# design.net
KiCad netlist of a schematic drawn in Altium Designer
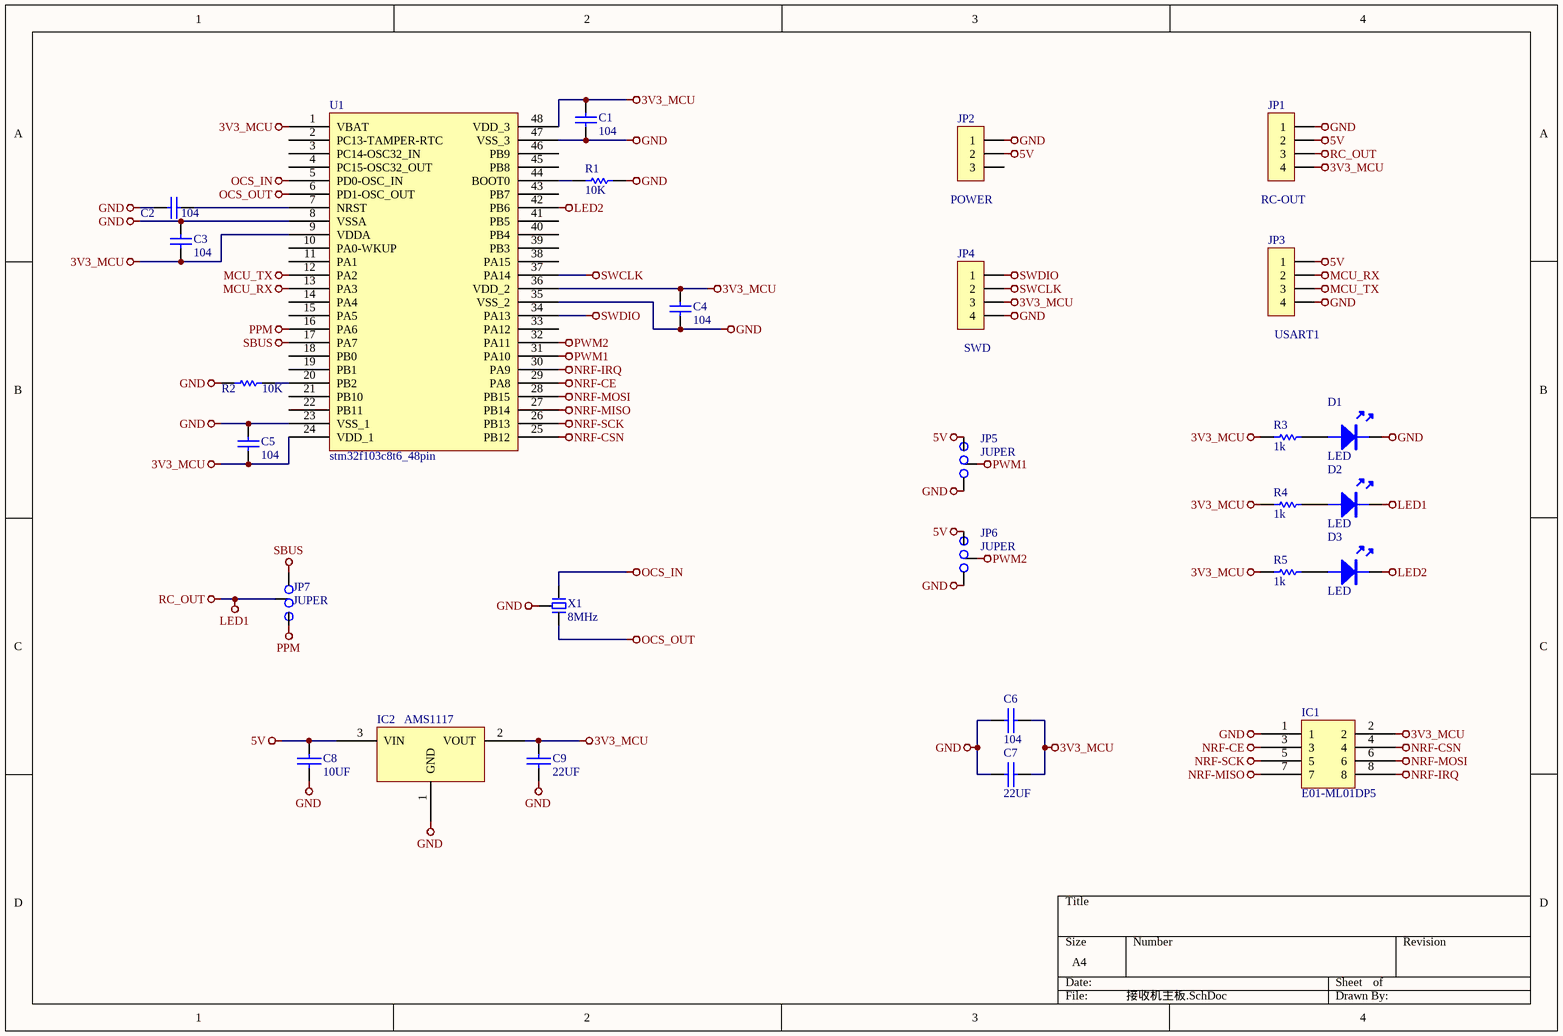
[diagram p0: 接收机主板.SchDoc]

(export (version "E")
  (design (tool "Eeschema 10.0.6"))
  (components
    (comp (ref "C1")
      (value "104")
      (footprint "0603C")
      (fields (field (name "PUBLISHER") "Altium Limited"))
      (libsource (lib "stm32原理图库") (part "Cap"))
    )
    (comp (ref "C2")
      (value "104")
      (footprint "0603C")
      (fields (field (name "PUBLISHER") "Altium Limited"))
      (libsource (lib "stm32原理图库") (part "Cap"))
    )
    (comp (ref "C3")
      (value "104")
      (footprint "0603C")
      (fields (field (name "PUBLISHER") "Altium Limited"))
      (libsource (lib "stm32原理图库") (part "Cap"))
    )
    (comp (ref "C4")
      (value "104")
      (footprint "0603C")
      (fields (field (name "PUBLISHER") "Altium Limited"))
      (libsource (lib "stm32原理图库") (part "Cap"))
    )
    (comp (ref "C5")
      (value "104")
      (footprint "0603C")
      (fields (field (name "PUBLISHER") "Altium Limited"))
      (libsource (lib "stm32原理图库") (part "Cap"))
    )
    (comp (ref "C6")
      (value "104")
      (footprint "0603C")
      (description "无极性电容")
      (libsource (lib "电容") (part "CAP"))
    )
    (comp (ref "C7")
      (value "22UF")
      (footprint "0603C")
      (description "无极性电容")
      (libsource (lib "电容") (part "CAP"))
    )
    (comp (ref "C8")
      (value "10UF")
      (footprint "0603C")
      (description "无极性电容")
      (libsource (lib "电容") (part "CAP"))
    )
    (comp (ref "C9")
      (value "22UF")
      (footprint "0603C")
      (description "无极性电容")
      (libsource (lib "电容") (part "CAP"))
    )
    (comp (ref "D1") (value "LED") (footprint "LED-0603G") (libsource (lib "LED") (part "LED")))
    (comp (ref "D2") (value "LED") (footprint "LED-0603G") (libsource (lib "LED") (part "LED")))
    (comp (ref "D3") (value "LED") (footprint "LED-0603G") (libsource (lib "LED") (part "LED")))
    (comp (ref "IC1")
      (value "E01-ML01DP5")
      (footprint "E01-ML01DP5")
      (description "2.4G无线模块")
      (libsource (lib "飞控接收机主板") (part "E01-ML01DP5"))
    )
    (comp (ref "IC2")
      (value "AMS1117")
      (footprint "AMS1117")
      (description "3V3降压芯片")
      (libsource (lib "飞控主板") (part "AMS1117"))
    )
    (comp (ref "JP1")
      (value "RC-OUT")
      (footprint "SH1.0 S-W-4P")
      (description "4P接插件")
      (fields (field (name "版权归属") "源创客"))
      (libsource (lib "ATKF405 V1.1") (part "Header 4"))
    )
    (comp (ref "JP2")
      (value "POWER")
      (footprint "MX 1.25-WS-3P")
      (description "3P接插件")
      (fields (field (name "版权归属") "源创客"))
      (libsource (lib "ATKF405 V1.1") (part "Header 3"))
    )
    (comp (ref "JP3")
      (value "USART1")
      (footprint "SH1.0 S-W-4P")
      (description "4P接插件")
      (fields (field (name "版权归属") "源创客"))
      (libsource (lib "ATKF405 V1.1") (part "Header 4"))
    )
    (comp (ref "JP4")
      (value "SWD")
      (footprint "SH1.0 S-W-4P")
      (description "4P接插件")
      (fields (field (name "版权归属") "源创客"))
      (libsource (lib "ATKF405 V1.1") (part "Header 4"))
    )
    (comp (ref "JP5")
      (value "JUPER")
      (footprint "JUMPER 3P")
      (description "三点焊盘跳线")
      (libsource (lib "ATKF405 V1.1") (part "JUMPER 3P"))
    )
    (comp (ref "JP6")
      (value "JUPER")
      (footprint "JUMPER 3P")
      (description "三点焊盘跳线")
      (libsource (lib "ATKF405 V1.1") (part "JUMPER 3P"))
    )
    (comp (ref "JP7")
      (value "JUPER")
      (footprint "JUMPER 3P")
      (description "三点焊盘跳线")
      (libsource (lib "ATKF405 V1.1") (part "JUMPER 3P"))
    )
    (comp (ref "R1") (value "10K") (footprint "0402R") (libsource (lib "电阻") (part "RES")))
    (comp (ref "R2") (value "10K") (footprint "0402R") (libsource (lib "电阻") (part "RES")))
    (comp (ref "R3") (value "1k") (footprint "0805R") (libsource (lib "电阻") (part "RES")))
    (comp (ref "R4") (value "1k") (footprint "0805R") (libsource (lib "电阻") (part "RES")))
    (comp (ref "R5") (value "1k") (footprint "0805R") (libsource (lib "电阻") (part "RES")))
    (comp (ref "U1")
      (value "stm32f103c8t6_48pin")
      (footprint "LQFP48 7X7")
      (libsource (lib "stm32原理图库") (part "stm32f103c8t6_48pin"))
    )
    (comp (ref "X1")
      (value "8MHz")
      (footprint "XTAL-3215-3P")
      (description "3脚无源晶振")
      (fields (field (name "版权归属") "源创客"))
      (libsource (lib "ATKF405 V1.1") (part "XTAL-3P"))
    )
  )
  (nets
    (net (code "1") (name "3V3_MCU") (class "Default")
      (node (ref "C1") (pin "2") (pinfunction "2_2") (pintype "passive"))
      (node (ref "C3") (pin "1") (pinfunction "1_1") (pintype "passive"))
      (node (ref "C4") (pin "2") (pinfunction "2_2") (pintype "passive"))
      (node (ref "C5") (pin "1") (pinfunction "1_1") (pintype "passive"))
      (node (ref "C6") (pin "2") (pinfunction "2_2") (pintype "passive"))
      (node (ref "C7") (pin "2") (pinfunction "2_2") (pintype "passive"))
      (node (ref "C9") (pin "2") (pinfunction "2_2") (pintype "passive"))
      (node (ref "IC1") (pin "2") (pinfunction "2_2") (pintype "passive"))
      (node (ref "IC2") (pin "2") (pinfunction "VOUT_2") (pintype "passive"))
      (node (ref "JP1") (pin "4") (pinfunction "4_4") (pintype "passive"))
      (node (ref "JP4") (pin "3") (pinfunction "3_3") (pintype "passive"))
      (node (ref "R3") (pin "1") (pinfunction "1_1") (pintype "passive"))
      (node (ref "R4") (pin "1") (pinfunction "1_1") (pintype "passive"))
      (node (ref "R5") (pin "1") (pinfunction "1_1") (pintype "passive"))
      (node (ref "U1") (pin "1") (pinfunction "VBAT_1") (pintype "passive"))
      (node (ref "U1") (pin "24") (pinfunction "VDD_1_24") (pintype "passive"))
      (node (ref "U1") (pin "36") (pinfunction "VDD_2_36") (pintype "passive"))
      (node (ref "U1") (pin "48") (pinfunction "VDD_3_48") (pintype "passive"))
      (node (ref "U1") (pin "9") (pinfunction "VDDA_9") (pintype "passive"))
    )
    (net (code "2") (name "5V") (class "Default")
      (node (ref "C8") (pin "2") (pinfunction "2_2") (pintype "passive"))
      (node (ref "IC2") (pin "3") (pinfunction "VIN_3") (pintype "passive"))
      (node (ref "JP1") (pin "2") (pinfunction "2_2") (pintype "passive"))
      (node (ref "JP2") (pin "2") (pinfunction "2_2") (pintype "passive"))
      (node (ref "JP3") (pin "1") (pinfunction "1_1") (pintype "passive"))
      (node (ref "JP5") (pin "3") (pinfunction "3_3") (pintype "passive"))
      (node (ref "JP6") (pin "3") (pinfunction "3_3") (pintype "passive"))
    )
    (net (code "3") (name "GND") (class "Default")
      (node (ref "C1") (pin "1") (pinfunction "1_1") (pintype "passive"))
      (node (ref "C2") (pin "2") (pinfunction "2_2") (pintype "passive"))
      (node (ref "C3") (pin "2") (pinfunction "2_2") (pintype "passive"))
      (node (ref "C4") (pin "1") (pinfunction "1_1") (pintype "passive"))
      (node (ref "C5") (pin "2") (pinfunction "2_2") (pintype "passive"))
      (node (ref "C6") (pin "1") (pinfunction "1_1") (pintype "passive"))
      (node (ref "C7") (pin "1") (pinfunction "1_1") (pintype "passive"))
      (node (ref "C8") (pin "1") (pinfunction "1_1") (pintype "passive"))
      (node (ref "C9") (pin "1") (pinfunction "1_1") (pintype "passive"))
      (node (ref "D1") (pin "K") (pinfunction "K_K") (pintype "passive"))
      (node (ref "IC1") (pin "1") (pinfunction "1_1") (pintype "passive"))
      (node (ref "IC2") (pin "1") (pinfunction "GND_1") (pintype "passive"))
      (node (ref "JP1") (pin "1") (pinfunction "1_1") (pintype "passive"))
      (node (ref "JP2") (pin "1") (pinfunction "1_1") (pintype "passive"))
      (node (ref "JP3") (pin "4") (pinfunction "4_4") (pintype "passive"))
      (node (ref "JP4") (pin "4") (pinfunction "4_4") (pintype "passive"))
      (node (ref "JP5") (pin "1") (pinfunction "1_1") (pintype "passive"))
      (node (ref "JP6") (pin "1") (pinfunction "1_1") (pintype "passive"))
      (node (ref "R1") (pin "2") (pinfunction "2_2") (pintype "passive"))
      (node (ref "R2") (pin "1") (pinfunction "1_1") (pintype "passive"))
      (node (ref "U1") (pin "23") (pinfunction "VSS_1_23") (pintype "passive"))
      (node (ref "U1") (pin "35") (pinfunction "VSS_2_35") (pintype "passive"))
      (node (ref "U1") (pin "47") (pinfunction "VSS_3_47") (pintype "passive"))
      (node (ref "U1") (pin "8") (pinfunction "VSSA_8") (pintype "passive"))
      (node (ref "X1") (pin "2") (pinfunction "2_2") (pintype "passive"))
    )
    (net (code "4") (name "LED1") (class "Default")
      (node (ref "D2") (pin "K") (pinfunction "K_K") (pintype "passive"))
      (node (ref "JP1") (pin "3") (pinfunction "3_3") (pintype "passive"))
      (node (ref "JP7") (pin "2") (pinfunction "2_2") (pintype "passive"))
    )
    (net (code "5") (name "LED2") (class "Default")
      (node (ref "D3") (pin "K") (pinfunction "K_K") (pintype "passive"))
      (node (ref "U1") (pin "42") (pinfunction "PB6_42") (pintype "passive"))
    )
    (net (code "6") (name "MCU_RX") (class "Default")
      (node (ref "JP3") (pin "2") (pinfunction "2_2") (pintype "passive"))
      (node (ref "U1") (pin "13") (pinfunction "PA3_13") (pintype "passive"))
    )
    (net (code "7") (name "MCU_TX") (class "Default")
      (node (ref "JP3") (pin "3") (pinfunction "3_3") (pintype "passive"))
      (node (ref "U1") (pin "12") (pinfunction "PA2_12") (pintype "passive"))
    )
    (net (code "8") (name "NRF-CE") (class "Default")
      (node (ref "IC1") (pin "3") (pinfunction "3_3") (pintype "passive"))
      (node (ref "U1") (pin "29") (pinfunction "PA8_29") (pintype "passive"))
    )
    (net (code "9") (name "NRF-CSN") (class "Default")
      (node (ref "IC1") (pin "4") (pinfunction "4_4") (pintype "passive"))
      (node (ref "U1") (pin "25") (pinfunction "PB12_25") (pintype "passive"))
    )
    (net (code "10") (name "NRF-IRQ") (class "Default")
      (node (ref "IC1") (pin "8") (pinfunction "8_8") (pintype "passive"))
      (node (ref "U1") (pin "30") (pinfunction "PA9_30") (pintype "passive"))
    )
    (net (code "11") (name "NRF-MISO") (class "Default")
      (node (ref "IC1") (pin "7") (pinfunction "7_7") (pintype "passive"))
      (node (ref "U1") (pin "27") (pinfunction "PB14_27") (pintype "passive"))
    )
    (net (code "12") (name "NRF-MOSI") (class "Default")
      (node (ref "IC1") (pin "6") (pinfunction "6_6") (pintype "passive"))
      (node (ref "U1") (pin "28") (pinfunction "PB15_28") (pintype "passive"))
    )
    (net (code "13") (name "NRF-SCK") (class "Default")
      (node (ref "IC1") (pin "5") (pinfunction "5_5") (pintype "passive"))
      (node (ref "U1") (pin "26") (pinfunction "PB13_26") (pintype "passive"))
    )
    (net (code "14") (name "Net-(D1-PadA)") (class "Default")
      (node (ref "D1") (pin "A") (pinfunction "A_A") (pintype "passive"))
      (node (ref "R3") (pin "2") (pinfunction "2_2") (pintype "passive"))
    )
    (net (code "15") (name "Net-(D2-PadA)") (class "Default")
      (node (ref "D2") (pin "A") (pinfunction "A_A") (pintype "passive"))
      (node (ref "R4") (pin "2") (pinfunction "2_2") (pintype "passive"))
    )
    (net (code "16") (name "Net-(D3-PadA)") (class "Default")
      (node (ref "D3") (pin "A") (pinfunction "A_A") (pintype "passive"))
      (node (ref "R5") (pin "2") (pinfunction "2_2") (pintype "passive"))
    )
    (net (code "17") (name "Net-(U1-BOOT0)") (class "Default")
      (node (ref "R1") (pin "1") (pinfunction "1_1") (pintype "passive"))
      (node (ref "U1") (pin "44") (pinfunction "BOOT0_44") (pintype "passive"))
    )
    (net (code "18") (name "Net-(U1-NRST)") (class "Default")
      (node (ref "C2") (pin "1") (pinfunction "1_1") (pintype "passive"))
      (node (ref "U1") (pin "7") (pinfunction "NRST_7") (pintype "passive"))
    )
    (net (code "19") (name "Net-(U1-PB2)") (class "Default")
      (node (ref "R2") (pin "2") (pinfunction "2_2") (pintype "passive"))
      (node (ref "U1") (pin "20") (pinfunction "PB2_20") (pintype "passive"))
    )
    (net (code "20") (name "OCS_IN") (class "Default")
      (node (ref "U1") (pin "5") (pinfunction "PD0-OSC_IN_5") (pintype "passive"))
      (node (ref "X1") (pin "1") (pinfunction "1_1") (pintype "passive"))
    )
    (net (code "21") (name "OCS_OUT") (class "Default")
      (node (ref "U1") (pin "6") (pinfunction "PD1-OSC_OUT_6") (pintype "passive"))
      (node (ref "X1") (pin "3") (pinfunction "3_3") (pintype "passive"))
    )
    (net (code "22") (name "PPM") (class "Default")
      (node (ref "JP7") (pin "3") (pinfunction "3_3") (pintype "passive"))
      (node (ref "U1") (pin "16") (pinfunction "PA6_16") (pintype "passive"))
    )
    (net (code "23") (name "PWM1") (class "Default")
      (node (ref "JP5") (pin "2") (pinfunction "2_2") (pintype "passive"))
      (node (ref "U1") (pin "31") (pinfunction "PA10_31") (pintype "passive"))
    )
    (net (code "24") (name "PWM2") (class "Default")
      (node (ref "JP6") (pin "2") (pinfunction "2_2") (pintype "passive"))
      (node (ref "U1") (pin "32") (pinfunction "PA11_32") (pintype "passive"))
    )
    (net (code "25") (name "SBUS") (class "Default")
      (node (ref "JP7") (pin "1") (pinfunction "1_1") (pintype "passive"))
      (node (ref "U1") (pin "17") (pinfunction "PA7_17") (pintype "passive"))
    )
    (net (code "26") (name "SWCLK") (class "Default")
      (node (ref "JP4") (pin "2") (pinfunction "2_2") (pintype "passive"))
      (node (ref "U1") (pin "37") (pinfunction "PA14_37") (pintype "passive"))
    )
    (net (code "27") (name "SWDIO") (class "Default")
      (node (ref "JP4") (pin "1") (pinfunction "1_1") (pintype "passive"))
      (node (ref "U1") (pin "34") (pinfunction "PA13_34") (pintype "passive"))
    )
    (net (code "28") (name "unconnected-(JP2-Pad3)") (class "Default")
      (node (ref "JP2") (pin "3") (pinfunction "3_3") (pintype "passive"))
    )
    (net (code "29") (name "unconnected-(U1-PA0-WKUP-Pad10)") (class "Default")
      (node (ref "U1") (pin "10") (pinfunction "PA0-WKUP_10") (pintype "passive"))
    )
    (net (code "30") (name "unconnected-(U1-PA1-Pad11)") (class "Default")
      (node (ref "U1") (pin "11") (pinfunction "PA1_11") (pintype "passive"))
    )
    (net (code "31") (name "unconnected-(U1-PA4-Pad14)") (class "Default")
      (node (ref "U1") (pin "14") (pinfunction "PA4_14") (pintype "passive"))
    )
    (net (code "32") (name "unconnected-(U1-PA5-Pad15)") (class "Default")
      (node (ref "U1") (pin "15") (pinfunction "PA5_15") (pintype "passive"))
    )
    (net (code "33") (name "unconnected-(U1-PA12-Pad33)") (class "Default")
      (node (ref "U1") (pin "33") (pinfunction "PA12_33") (pintype "passive"))
    )
    (net (code "34") (name "unconnected-(U1-PA15-Pad38)") (class "Default")
      (node (ref "U1") (pin "38") (pinfunction "PA15_38") (pintype "passive"))
    )
    (net (code "35") (name "unconnected-(U1-PB0-Pad18)") (class "Default")
      (node (ref "U1") (pin "18") (pinfunction "PB0_18") (pintype "passive"))
    )
    (net (code "36") (name "unconnected-(U1-PB1-Pad19)") (class "Default")
      (node (ref "U1") (pin "19") (pinfunction "PB1_19") (pintype "passive"))
    )
    (net (code "37") (name "unconnected-(U1-PB3-Pad39)") (class "Default")
      (node (ref "U1") (pin "39") (pinfunction "PB3_39") (pintype "passive"))
    )
    (net (code "38") (name "unconnected-(U1-PB4-Pad40)") (class "Default")
      (node (ref "U1") (pin "40") (pinfunction "PB4_40") (pintype "passive"))
    )
    (net (code "39") (name "unconnected-(U1-PB5-Pad41)") (class "Default")
      (node (ref "U1") (pin "41") (pinfunction "PB5_41") (pintype "passive"))
    )
    (net (code "40") (name "unconnected-(U1-PB7-Pad43)") (class "Default")
      (node (ref "U1") (pin "43") (pinfunction "PB7_43") (pintype "passive"))
    )
    (net (code "41") (name "unconnected-(U1-PB8-Pad45)") (class "Default")
      (node (ref "U1") (pin "45") (pinfunction "PB8_45") (pintype "passive"))
    )
    (net (code "42") (name "unconnected-(U1-PB9-Pad46)") (class "Default")
      (node (ref "U1") (pin "46") (pinfunction "PB9_46") (pintype "passive"))
    )
    (net (code "43") (name "unconnected-(U1-PB10-Pad21)") (class "Default")
      (node (ref "U1") (pin "21") (pinfunction "PB10_21") (pintype "passive"))
    )
    (net (code "44") (name "unconnected-(U1-PB11-Pad22)") (class "Default")
      (node (ref "U1") (pin "22") (pinfunction "PB11_22") (pintype "passive"))
    )
    (net (code "45") (name "unconnected-(U1-PC13-TAMPER-RTC-Pad2)") (class "Default")
      (node (ref "U1") (pin "2") (pinfunction "PC13-TAMPER-RTC_2") (pintype "passive"))
    )
    (net (code "46") (name "unconnected-(U1-PC14-OSC32_IN-Pad3)") (class "Default")
      (node (ref "U1") (pin "3") (pinfunction "PC14-OSC32_IN_3") (pintype "passive"))
    )
    (net (code "47") (name "unconnected-(U1-PC15-OSC32_OUT-Pad4)") (class "Default")
      (node (ref "U1") (pin "4") (pinfunction "PC15-OSC32_OUT_4") (pintype "passive"))
    )
  )
)
